# EXP430FR2433_devBoard.net
KiCad netlist of a schematic drawn in EAGLE
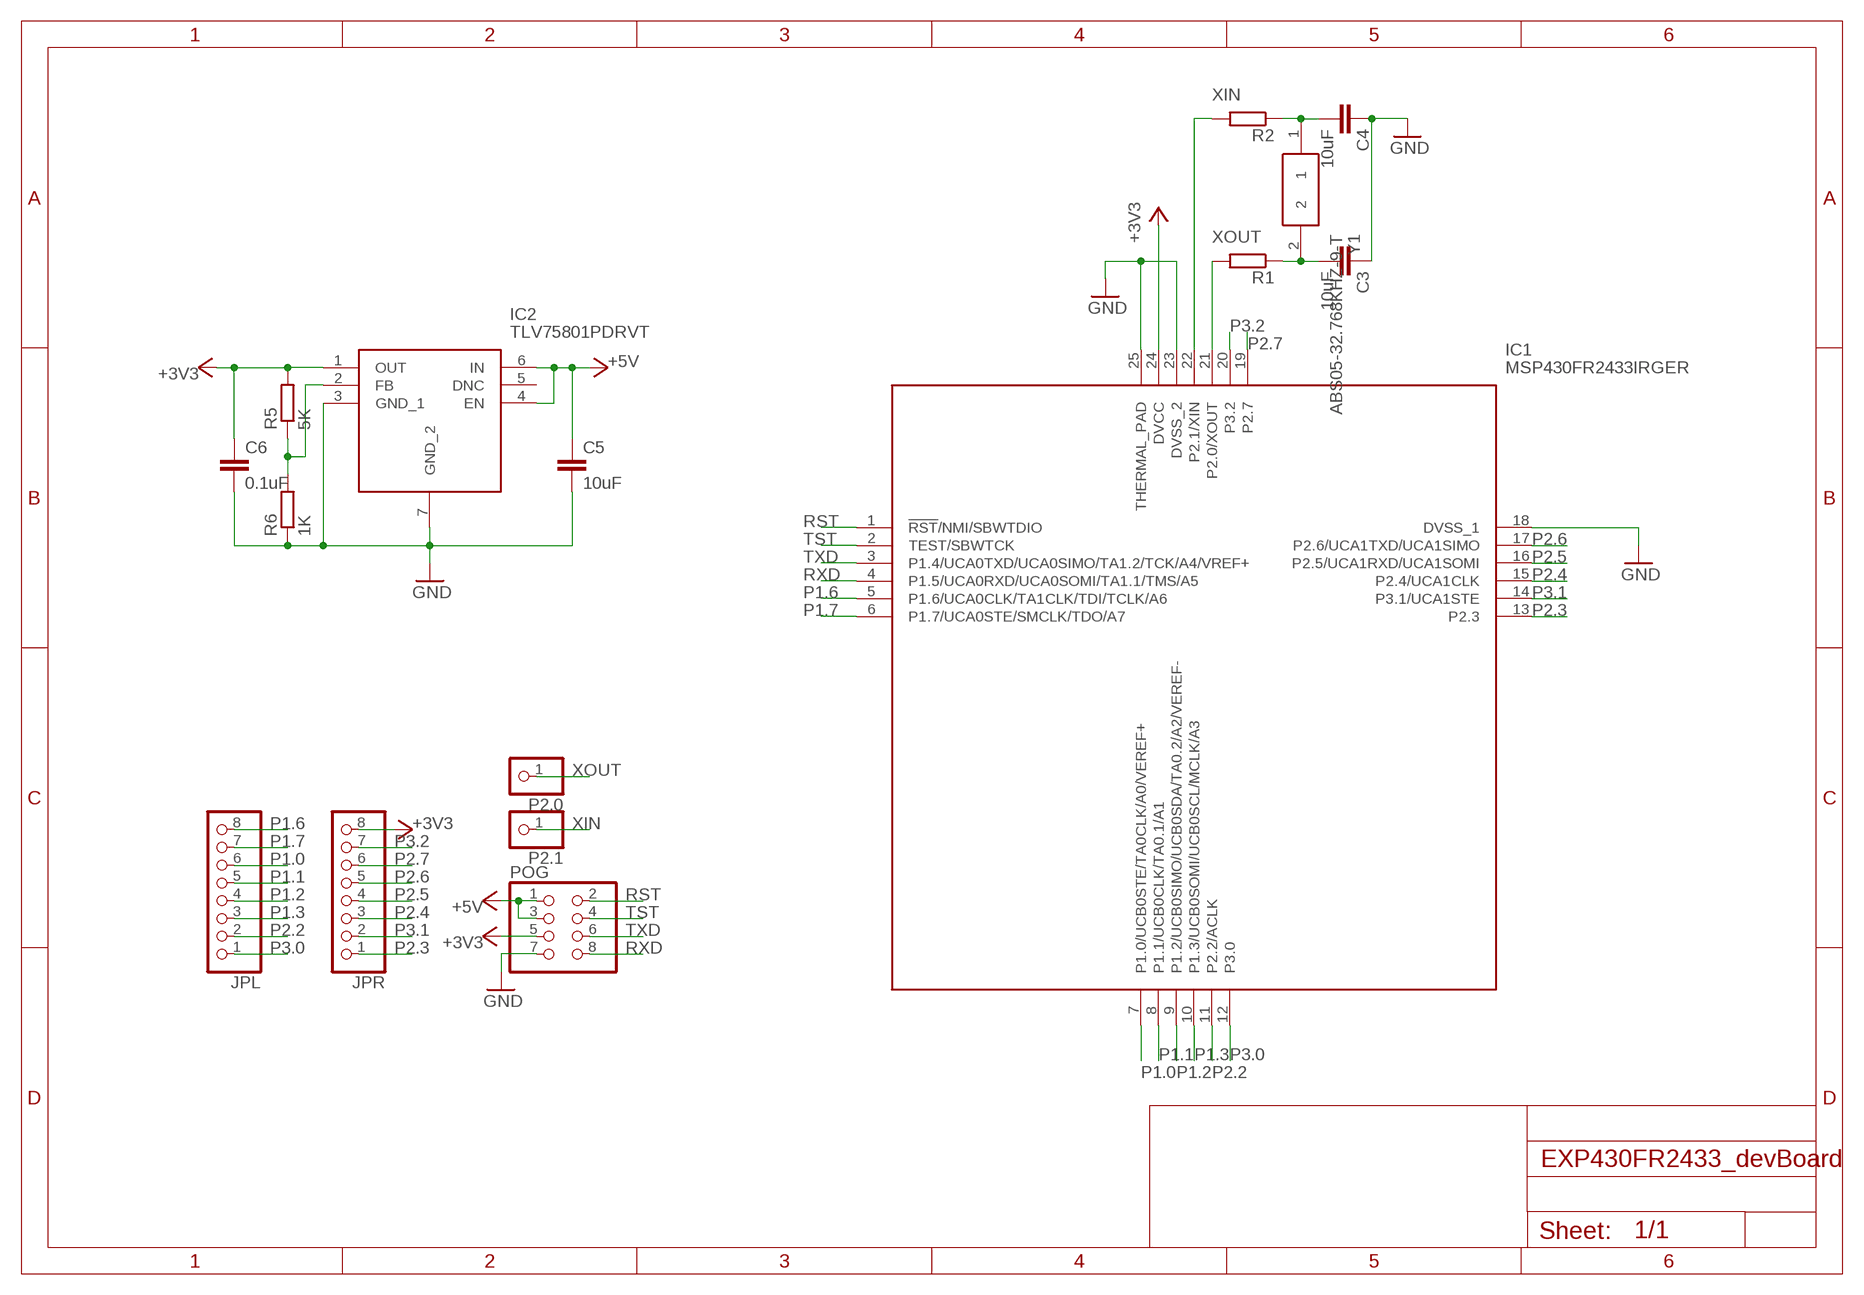
[diagram p0: schematic, sheet 1]

(export (version "E")
  (design (tool "Eeschema 10.0.6"))
  (components
    (comp (ref "C3")
      (value "10uF")
      (footprint "eagle-import:C0805K")
      (libsource (lib "eagle-import") (part "C-EUC0805K"))
    )
    (comp (ref "C4")
      (value "10uF")
      (footprint "eagle-import:C0805K")
      (libsource (lib "eagle-import") (part "C-EUC0805K"))
    )
    (comp (ref "C5")
      (value "10uF")
      (footprint "eagle-import:C0805K")
      (libsource (lib "eagle-import") (part "C-EUC0805K"))
    )
    (comp (ref "C6")
      (value "0.1uF")
      (footprint "eagle-import:C0805K")
      (libsource (lib "eagle-import") (part "C-EUC0805K"))
    )
    (comp (ref "IC1")
      (value "MSP430FR2433IRGER")
      (footprint "eagle-import:QFN50P400X400X100-25N")
      (fields (field (name "MOUSER_PART_NUMBER") "595-SP430FR2433IRGER"))
      (libsource (lib "eagle-import") (part "MSP430FR2433IRGER"))
    )
    (comp (ref "IC2")
      (value "TLV75801PDRVT")
      (footprint "eagle-import:SON65P200X200X80-7N")
      (fields (field (name "MOUSER_PART_NUMBER") "595-TLV75801PDRVT"))
      (libsource (lib "eagle-import") (part "TLV75801PDRVT"))
    )
    (comp (ref "JPL")
      (value "PINHD-1X8")
      (footprint "eagle-import:1X08")
      (libsource (lib "eagle-import") (part "PINHD-1X8"))
    )
    (comp (ref "JPR")
      (value "PINHD-1X8")
      (footprint "eagle-import:1X08")
      (libsource (lib "eagle-import") (part "PINHD-1X8"))
    )
    (comp (ref "P2.0")
      (value "PINHD-1X1")
      (footprint "eagle-import:1X01")
      (libsource (lib "eagle-import") (part "PINHD-1X1"))
    )
    (comp (ref "P2.1")
      (value "PINHD-1X1")
      (footprint "eagle-import:1X01")
      (libsource (lib "eagle-import") (part "PINHD-1X1"))
    )
    (comp (ref "POG")
      (value "PINHD-2X4")
      (footprint "eagle-import:2X04")
      (libsource (lib "eagle-import") (part "PINHD-2X4"))
    )
    (comp (ref "R1")
      (value "R-EU_R0402")
      (footprint "eagle-import:R0402")
      (libsource (lib "eagle-import") (part "R-EU_R0402"))
    )
    (comp (ref "R2")
      (value "R-EU_R0402")
      (footprint "eagle-import:R0402")
      (libsource (lib "eagle-import") (part "R-EU_R0402"))
    )
    (comp (ref "R5")
      (value "5K")
      (footprint "eagle-import:R0805")
      (libsource (lib "eagle-import") (part "R-EU_R0805"))
    )
    (comp (ref "R6")
      (value "1K")
      (footprint "eagle-import:R0805")
      (libsource (lib "eagle-import") (part "R-EU_R0805"))
    )
    (comp (ref "Y1")
      (value "ABS05-32.768KHZ-9-T")
      (footprint "eagle-import:ABS05")
      (fields (field (name "MOUSER_PART_NUMBER") "815-ABS05-32.768K9T"))
      (libsource (lib "eagle-import") (part "ABS05-32.768KHZ-9-T"))
    )
  )
  (nets
    (net (code "1") (name "+3V3") (class "Default")
      (node (ref "C6") (pin "1") (pinfunction "1_1") (pintype "passive"))
      (node (ref "IC1") (pin "24") (pinfunction "DVCC_24") (pintype "bidirectional"))
      (node (ref "IC2") (pin "1") (pinfunction "OUT_1") (pintype "bidirectional"))
      (node (ref "JPR") (pin "8") (pinfunction "8_8") (pintype "passive"))
      (node (ref "POG") (pin "5") (pinfunction "5_5") (pintype "passive"))
      (node (ref "R5") (pin "2") (pinfunction "2_2") (pintype "passive"))
    )
    (net (code "2") (name "+5V") (class "Default")
      (node (ref "C5") (pin "1") (pinfunction "1_1") (pintype "passive"))
      (node (ref "IC2") (pin "4") (pinfunction "EN_4") (pintype "bidirectional"))
      (node (ref "IC2") (pin "6") (pinfunction "IN_6") (pintype "bidirectional"))
      (node (ref "POG") (pin "1") (pinfunction "1_1") (pintype "passive"))
      (node (ref "POG") (pin "3") (pinfunction "3_3") (pintype "passive"))
    )
    (net (code "3") (name "/P1.0") (class "Default")
      (node (ref "IC1") (pin "7") (pinfunction "P1.0/UCB0STE/TA0CLK/A0/VEREF+_7") (pintype "bidirectional"))
      (node (ref "JPL") (pin "6") (pinfunction "6_6") (pintype "passive"))
    )
    (net (code "4") (name "/P1.1") (class "Default")
      (node (ref "IC1") (pin "8") (pinfunction "P1.1/UCB0CLK/TA0.1/A1_8") (pintype "bidirectional"))
      (node (ref "JPL") (pin "5") (pinfunction "5_5") (pintype "passive"))
    )
    (net (code "5") (name "/P1.2") (class "Default")
      (node (ref "IC1") (pin "9") (pinfunction "P1.2/UCB0SIMO/UCB0SDA/TA0.2/A2/VEREF-_9") (pintype "bidirectional"))
      (node (ref "JPL") (pin "4") (pinfunction "4_4") (pintype "passive"))
    )
    (net (code "6") (name "/P1.3") (class "Default")
      (node (ref "IC1") (pin "10") (pinfunction "P1.3/UCB0SOMI/UCB0SCL/MCLK/A3_10") (pintype "bidirectional"))
      (node (ref "JPL") (pin "3") (pinfunction "3_3") (pintype "passive"))
    )
    (net (code "7") (name "/P1.6") (class "Default")
      (node (ref "IC1") (pin "5") (pinfunction "P1.6/UCA0CLK/TA1CLK/TDI/TCLK/A6_5") (pintype "bidirectional"))
      (node (ref "JPL") (pin "8") (pinfunction "8_8") (pintype "passive"))
    )
    (net (code "8") (name "/P1.7") (class "Default")
      (node (ref "IC1") (pin "6") (pinfunction "P1.7/UCA0STE/SMCLK/TDO/A7_6") (pintype "bidirectional"))
      (node (ref "JPL") (pin "7") (pinfunction "7_7") (pintype "passive"))
    )
    (net (code "9") (name "/P2.2") (class "Default")
      (node (ref "IC1") (pin "11") (pinfunction "P2.2/ACLK_11") (pintype "bidirectional"))
      (node (ref "JPL") (pin "2") (pinfunction "2_2") (pintype "passive"))
    )
    (net (code "10") (name "/P2.3") (class "Default")
      (node (ref "IC1") (pin "13") (pinfunction "P2.3_13") (pintype "bidirectional"))
      (node (ref "JPR") (pin "1") (pinfunction "1_1") (pintype "passive"))
    )
    (net (code "11") (name "/P2.4") (class "Default")
      (node (ref "IC1") (pin "15") (pinfunction "P2.4/UCA1CLK_15") (pintype "bidirectional"))
      (node (ref "JPR") (pin "3") (pinfunction "3_3") (pintype "passive"))
    )
    (net (code "12") (name "/P2.5") (class "Default")
      (node (ref "IC1") (pin "16") (pinfunction "P2.5/UCA1RXD/UCA1SOMI_16") (pintype "bidirectional"))
      (node (ref "JPR") (pin "4") (pinfunction "4_4") (pintype "passive"))
    )
    (net (code "13") (name "/P2.6") (class "Default")
      (node (ref "IC1") (pin "17") (pinfunction "P2.6/UCA1TXD/UCA1SIMO_17") (pintype "bidirectional"))
      (node (ref "JPR") (pin "5") (pinfunction "5_5") (pintype "passive"))
    )
    (net (code "14") (name "/P2.7") (class "Default")
      (node (ref "IC1") (pin "19") (pinfunction "P2.7_19") (pintype "bidirectional"))
      (node (ref "JPR") (pin "6") (pinfunction "6_6") (pintype "passive"))
    )
    (net (code "15") (name "/P3.0") (class "Default")
      (node (ref "IC1") (pin "12") (pinfunction "P3.0_12") (pintype "bidirectional"))
      (node (ref "JPL") (pin "1") (pinfunction "1_1") (pintype "passive"))
    )
    (net (code "16") (name "/P3.1") (class "Default")
      (node (ref "IC1") (pin "14") (pinfunction "P3.1/UCA1STE_14") (pintype "bidirectional"))
      (node (ref "JPR") (pin "2") (pinfunction "2_2") (pintype "passive"))
    )
    (net (code "17") (name "/P3.2") (class "Default")
      (node (ref "IC1") (pin "20") (pinfunction "P3.2_20") (pintype "bidirectional"))
      (node (ref "JPR") (pin "7") (pinfunction "7_7") (pintype "passive"))
    )
    (net (code "18") (name "/RST") (class "Default")
      (node (ref "IC1") (pin "1") (pinfunction "~{RST}/NMI/SBWTDIO_1") (pintype "bidirectional"))
      (node (ref "POG") (pin "2") (pinfunction "2_2") (pintype "passive"))
    )
    (net (code "19") (name "/RXD") (class "Default")
      (node (ref "IC1") (pin "4") (pinfunction "P1.5/UCA0RXD/UCA0SOMI/TA1.1/TMS/A5_4") (pintype "bidirectional"))
      (node (ref "POG") (pin "8") (pinfunction "8_8") (pintype "passive"))
    )
    (net (code "20") (name "/TST") (class "Default")
      (node (ref "IC1") (pin "2") (pinfunction "TEST/SBWTCK_2") (pintype "bidirectional"))
      (node (ref "POG") (pin "4") (pinfunction "4_4") (pintype "passive"))
    )
    (net (code "21") (name "/TXD") (class "Default")
      (node (ref "IC1") (pin "3") (pinfunction "P1.4/UCA0TXD/UCA0SIMO/TA1.2/TCK/A4/VREF+_3") (pintype "bidirectional"))
      (node (ref "POG") (pin "6") (pinfunction "6_6") (pintype "passive"))
    )
    (net (code "22") (name "/XIN") (class "Default")
      (node (ref "IC1") (pin "22") (pinfunction "P2.1/XIN_22") (pintype "bidirectional"))
      (node (ref "P2.1") (pin "1") (pinfunction "1_1") (pintype "passive"))
      (node (ref "R2") (pin "2") (pinfunction "2_2") (pintype "passive"))
    )
    (net (code "23") (name "/XOUT") (class "Default")
      (node (ref "IC1") (pin "21") (pinfunction "P2.0/XOUT_21") (pintype "bidirectional"))
      (node (ref "P2.0") (pin "1") (pinfunction "1_1") (pintype "passive"))
      (node (ref "R1") (pin "2") (pinfunction "2_2") (pintype "passive"))
    )
    (net (code "24") (name "GND") (class "Default")
      (node (ref "C3") (pin "1") (pinfunction "1_1") (pintype "passive"))
      (node (ref "C4") (pin "1") (pinfunction "1_1") (pintype "passive"))
      (node (ref "C5") (pin "2") (pinfunction "2_2") (pintype "passive"))
      (node (ref "C6") (pin "2") (pinfunction "2_2") (pintype "passive"))
      (node (ref "IC1") (pin "18") (pinfunction "DVSS_1_18") (pintype "bidirectional"))
      (node (ref "IC1") (pin "23") (pinfunction "DVSS_2_23") (pintype "bidirectional"))
      (node (ref "IC1") (pin "25") (pinfunction "THERMAL_PAD_25") (pintype "bidirectional"))
      (node (ref "IC2") (pin "3") (pinfunction "GND_1_3") (pintype "bidirectional"))
      (node (ref "IC2") (pin "7") (pinfunction "GND_2_7") (pintype "bidirectional"))
      (node (ref "POG") (pin "7") (pinfunction "7_7") (pintype "passive"))
      (node (ref "R6") (pin "1") (pinfunction "1_1") (pintype "passive"))
    )
    (net (code "25") (name "Net-(C3-Pad2)") (class "Default")
      (node (ref "C3") (pin "2") (pinfunction "2_2") (pintype "passive"))
      (node (ref "R1") (pin "1") (pinfunction "1_1") (pintype "passive"))
      (node (ref "Y1") (pin "2") (pinfunction "2_2") (pintype "bidirectional"))
    )
    (net (code "26") (name "Net-(C4-Pad2)") (class "Default")
      (node (ref "C4") (pin "2") (pinfunction "2_2") (pintype "passive"))
      (node (ref "R2") (pin "1") (pinfunction "1_1") (pintype "passive"))
      (node (ref "Y1") (pin "1") (pinfunction "1_1") (pintype "bidirectional"))
    )
    (net (code "27") (name "Net-(IC2-FB)") (class "Default")
      (node (ref "IC2") (pin "2") (pinfunction "FB_2") (pintype "bidirectional"))
      (node (ref "R5") (pin "1") (pinfunction "1_1") (pintype "passive"))
      (node (ref "R6") (pin "2") (pinfunction "2_2") (pintype "passive"))
    )
    (net (code "28") (name "unconnected-(IC2-DNC-Pad5)") (class "Default")
      (node (ref "IC2") (pin "5") (pinfunction "DNC_5") (pintype "bidirectional"))
    )
  )
)
